# Sheet1.net
KiCad netlist of a schematic drawn in Altium Designer
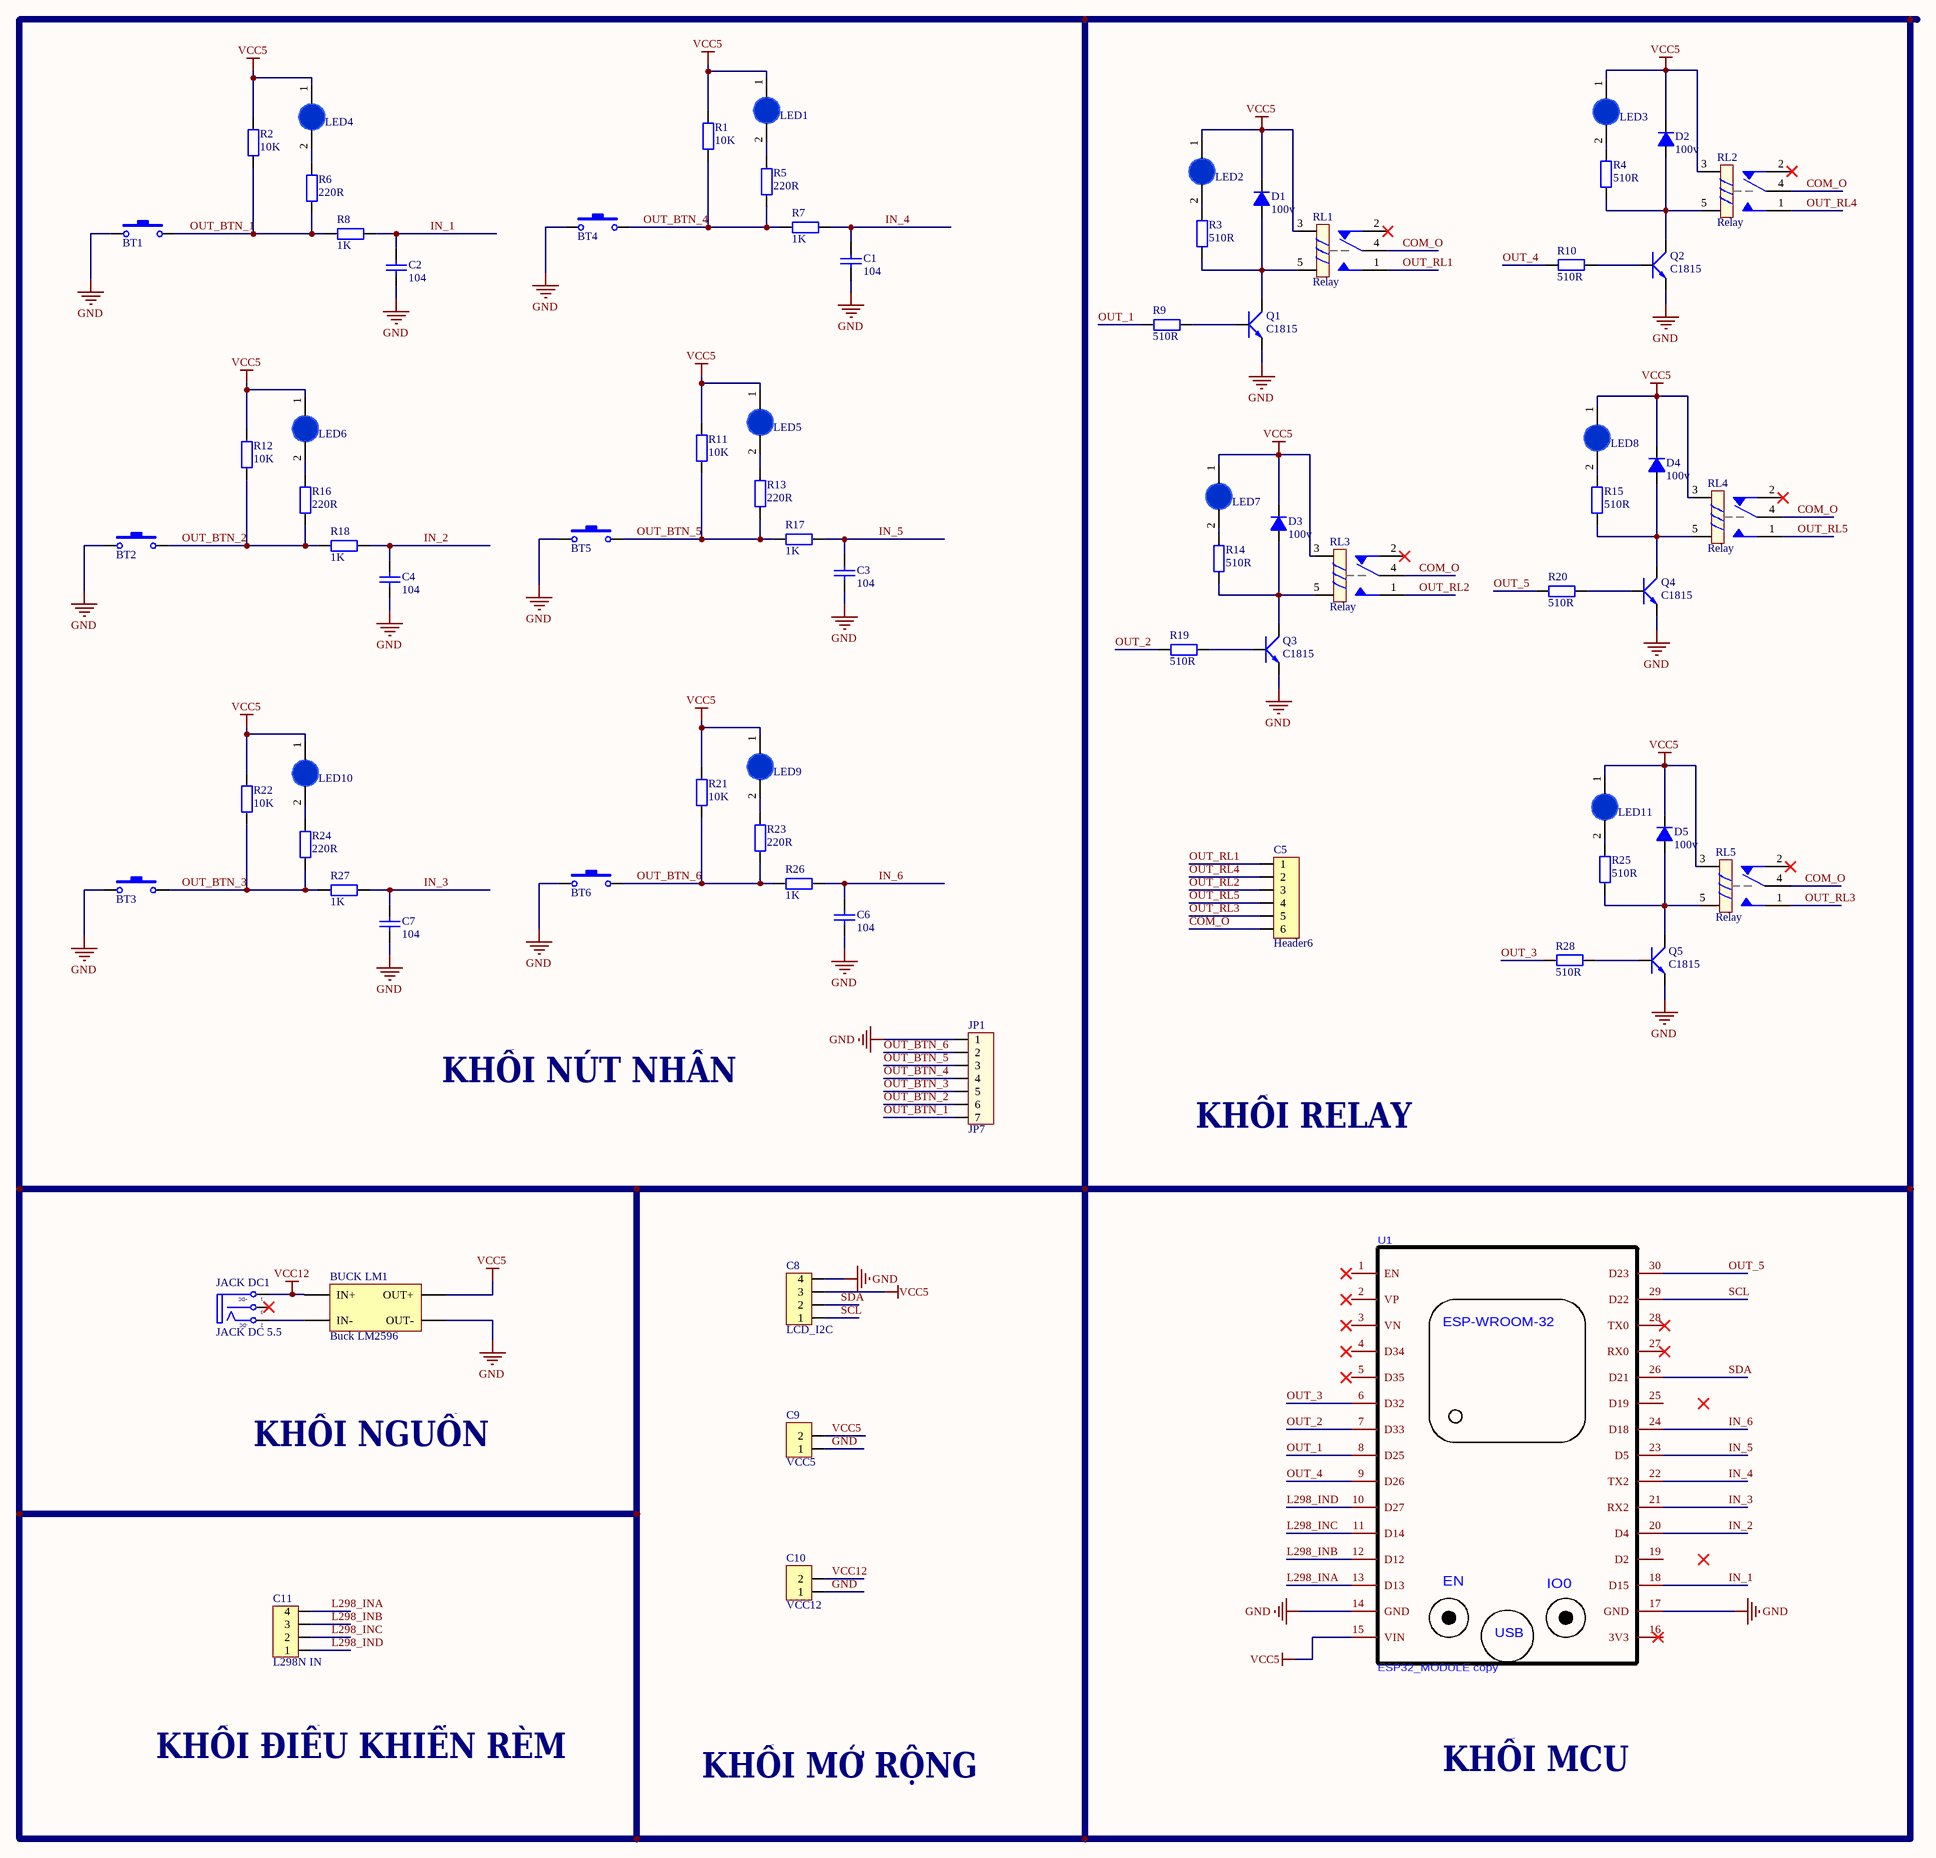
[diagram p0: Sheet1.SchDoc]

(export (version "E")
  (design (tool "Eeschema 10.0.6"))
  (components
    (comp (ref "BT1")
      (value "Nut Nhan 2 Chan SMD 3x6x2.5")
      (footprint "Nut Nhan 2 Chan SMD 3x6x2.5")
      (libsource (lib "Altium_Lib_by_KhueNguyenCreator") (part "Nut Nhan 2 Chan SMD 3x6x2.5"))
    )
    (comp (ref "BT2")
      (value "Nut Nhan 2 Chan SMD 3x6x2.5")
      (footprint "Nut Nhan 2 Chan SMD 3x6x2.5")
      (libsource (lib "Altium_Lib_by_KhueNguyenCreator") (part "Nut Nhan 2 Chan SMD 3x6x2.5"))
    )
    (comp (ref "BT3")
      (value "Nut Nhan 2 Chan SMD 3x6x2.5")
      (footprint "Nut Nhan 2 Chan SMD 3x6x2.5")
      (libsource (lib "Altium_Lib_by_KhueNguyenCreator") (part "Nut Nhan 2 Chan SMD 3x6x2.5"))
    )
    (comp (ref "BT4")
      (value "Nut Nhan 2 Chan SMD 3x6x2.5")
      (footprint "Nut Nhan 2 Chan SMD 3x6x2.5")
      (libsource (lib "Altium_Lib_by_KhueNguyenCreator") (part "Nut Nhan 2 Chan SMD 3x6x2.5"))
    )
    (comp (ref "BT5")
      (value "Nut Nhan 2 Chan SMD 3x6x2.5")
      (footprint "Nut Nhan 2 Chan SMD 3x6x2.5")
      (libsource (lib "Altium_Lib_by_KhueNguyenCreator") (part "Nut Nhan 2 Chan SMD 3x6x2.5"))
    )
    (comp (ref "BT6")
      (value "Nut Nhan 2 Chan SMD 3x6x2.5")
      (footprint "Nut Nhan 2 Chan SMD 3x6x2.5")
      (libsource (lib "Altium_Lib_by_KhueNguyenCreator") (part "Nut Nhan 2 Chan SMD 3x6x2.5"))
    )
    (comp (ref "BUCK LM1")
      (value "Buck LM2596")
      (footprint "BUCK LM2596")
      (libsource (lib "myLib_v1") (part "Buck LM2596"))
    )
    (comp (ref "C1")
      (value "104")
      (footprint "tu gom")
      (description "Cắm")
      (libsource (lib "Altium_Lib_by_KhueNguyenCreator") (part "Tu gom 104 50V"))
    )
    (comp (ref "C2")
      (value "104")
      (footprint "tu gom")
      (description "Cắm")
      (libsource (lib "Altium_Lib_by_KhueNguyenCreator") (part "Tu gom 104 50V"))
    )
    (comp (ref "C3")
      (value "104")
      (footprint "tu gom")
      (description "Cắm")
      (libsource (lib "Altium_Lib_by_KhueNguyenCreator") (part "Tu gom 104 50V"))
    )
    (comp (ref "C4")
      (value "104")
      (footprint "tu gom")
      (description "Cắm")
      (libsource (lib "Altium_Lib_by_KhueNguyenCreator") (part "Tu gom 104 50V"))
    )
    (comp (ref "C5")
      (value "Header6")
      (footprint "Header6")
      (description "Header IDC, 6 x 1 Pin Vertical 2.54mm Pitch (Non-Boxed, Male)")
      (fields
        (field (name "MANUFACTURER") "Würth Elektronik eiSos GmbH")
        (field (name "PARTNO") "613002143121")
        (field (name "CREATED BY") "Karrer Zheng")
      )
      (libsource (lib "myLib_v1") (part "Header6"))
    )
    (comp (ref "C6")
      (value "104")
      (footprint "tu gom")
      (description "Cắm")
      (libsource (lib "Altium_Lib_by_KhueNguyenCreator") (part "Tu gom 104 50V"))
    )
    (comp (ref "C7")
      (value "104")
      (footprint "tu gom")
      (description "Cắm")
      (libsource (lib "Altium_Lib_by_KhueNguyenCreator") (part "Tu gom 104 50V"))
    )
    (comp (ref "C8")
      (value "LCD_I2C")
      (footprint "Header4")
      (description "Header IDC, 4 x 1 Pin Vertical 2.54mm Pitch (Non-Boxed, Male)")
      (fields
        (field (name "MANUFACTURER") "Würth Elektronik eiSos GmbH")
        (field (name "PARTNO") "613002143121")
        (field (name "CREATED BY") "Karrer Zheng")
      )
      (libsource (lib "myLib_v1") (part "Header4"))
    )
    (comp (ref "C9")
      (value "VCC5")
      (footprint "Header2")
      (description "Header IDC, 2 x 1 Pin Vertical 2.54mm Pitch (Non-Boxed, Male)")
      (fields
        (field (name "MANUFACTURER") "Würth Elektronik eiSos GmbH")
        (field (name "PARTNO") "613002143121")
        (field (name "CREATED BY") "Karrer Zheng")
      )
      (libsource (lib "myLib_v1") (part "Header2"))
    )
    (comp (ref "C10")
      (value "VCC12")
      (footprint "Header2")
      (description "Header IDC, 2 x 1 Pin Vertical 2.54mm Pitch (Non-Boxed, Male)")
      (fields
        (field (name "MANUFACTURER") "Würth Elektronik eiSos GmbH")
        (field (name "PARTNO") "613002143121")
        (field (name "CREATED BY") "Karrer Zheng")
      )
      (libsource (lib "myLib_v1") (part "Header2"))
    )
    (comp (ref "C11")
      (value "L298N IN")
      (footprint "Header4")
      (description "Header IDC, 4 x 1 Pin Vertical 2.54mm Pitch (Non-Boxed, Male)")
      (fields
        (field (name "MANUFACTURER") "Würth Elektronik eiSos GmbH")
        (field (name "PARTNO") "613002143121")
        (field (name "CREATED BY") "Karrer Zheng")
      )
      (libsource (lib "myLib_v1") (part "Header4"))
    )
    (comp (ref "D1")
      (value "100v")
      (footprint "DIODE 0.5A")
      (description "Cắm")
      (libsource (lib "Altium_Lib_by_KhueNguyenCreator") (part "Diode 1N4148"))
    )
    (comp (ref "D2")
      (value "100v")
      (footprint "DIODE 0.5A")
      (description "Cắm")
      (libsource (lib "Altium_Lib_by_KhueNguyenCreator") (part "Diode 1N4148"))
    )
    (comp (ref "D3")
      (value "100v")
      (footprint "DIODE 0.5A")
      (description "Cắm")
      (libsource (lib "Altium_Lib_by_KhueNguyenCreator") (part "Diode 1N4148"))
    )
    (comp (ref "D4")
      (value "100v")
      (footprint "DIODE 0.5A")
      (description "Cắm")
      (libsource (lib "Altium_Lib_by_KhueNguyenCreator") (part "Diode 1N4148"))
    )
    (comp (ref "D5")
      (value "100v")
      (footprint "DIODE 0.5A")
      (description "Cắm")
      (libsource (lib "Altium_Lib_by_KhueNguyenCreator") (part "Diode 1N4148"))
    )
    (comp (ref "JACK DC1")
      (value "JACK DC 5.5")
      (footprint "JACK DC 5.5")
      (libsource (lib "Altium_Lib_by_KhueNguyenCreator") (part "JACK DC 5.5"))
    )
    (comp (ref "JP1")
      (value "JP7")
      (footprint "Header7")
      (description "Connector 7")
      (libsource (lib "myLib_v1") (part "Header7"))
    )
    (comp (ref "LED1")
      (value "LED 3mm")
      (footprint "LED-3MM-BLUE")
      (description "Cắm")
      (libsource (lib "myLib_v1") (part "LED 3mm Xanh Duong"))
    )
    (comp (ref "LED2")
      (value "LED 3mm")
      (footprint "LED-3MM-BLUE")
      (description "Cắm")
      (libsource (lib "myLib_v1") (part "LED 3mm Xanh Duong"))
    )
    (comp (ref "LED3")
      (value "LED 3mm")
      (footprint "LED-3MM-BLUE")
      (description "Cắm")
      (libsource (lib "myLib_v1") (part "LED 3mm Xanh Duong"))
    )
    (comp (ref "LED4")
      (value "LED 3mm")
      (footprint "LED-3MM-BLUE")
      (description "Cắm")
      (libsource (lib "myLib_v1") (part "LED 3mm Xanh Duong"))
    )
    (comp (ref "LED5")
      (value "LED 3mm")
      (footprint "LED-3MM-BLUE")
      (description "Cắm")
      (libsource (lib "myLib_v1") (part "LED 3mm Xanh Duong"))
    )
    (comp (ref "LED6")
      (value "LED 3mm")
      (footprint "LED-3MM-BLUE")
      (description "Cắm")
      (libsource (lib "myLib_v1") (part "LED 3mm Xanh Duong"))
    )
    (comp (ref "LED7")
      (value "LED 3mm")
      (footprint "LED-3MM-BLUE")
      (description "Cắm")
      (libsource (lib "myLib_v1") (part "LED 3mm Xanh Duong"))
    )
    (comp (ref "LED8")
      (value "LED 3mm")
      (footprint "LED-3MM-BLUE")
      (description "Cắm")
      (libsource (lib "myLib_v1") (part "LED 3mm Xanh Duong"))
    )
    (comp (ref "LED9")
      (value "LED 3mm")
      (footprint "LED-3MM-BLUE")
      (description "Cắm")
      (libsource (lib "myLib_v1") (part "LED 3mm Xanh Duong"))
    )
    (comp (ref "LED10")
      (value "LED 3mm")
      (footprint "LED-3MM-BLUE")
      (description "Cắm")
      (libsource (lib "myLib_v1") (part "LED 3mm Xanh Duong"))
    )
    (comp (ref "LED11")
      (value "LED 3mm")
      (footprint "LED-3MM-BLUE")
      (description "Cắm")
      (libsource (lib "myLib_v1") (part "LED 3mm Xanh Duong"))
    )
    (comp (ref "Q1")
      (value "C1815")
      (footprint "C1815_cam")
      (description "NPN 600mW, ECB")
      (libsource (lib "myLib_v1") (part "C1815"))
    )
    (comp (ref "Q2")
      (value "C1815")
      (footprint "C1815_cam")
      (description "NPN 600mW, ECB")
      (libsource (lib "myLib_v1") (part "C1815"))
    )
    (comp (ref "Q3")
      (value "C1815")
      (footprint "C1815_cam")
      (description "NPN 600mW, ECB")
      (libsource (lib "myLib_v1") (part "C1815"))
    )
    (comp (ref "Q4")
      (value "C1815")
      (footprint "C1815_cam")
      (description "NPN 600mW, ECB")
      (libsource (lib "myLib_v1") (part "C1815"))
    )
    (comp (ref "Q5")
      (value "C1815")
      (footprint "C1815_cam")
      (description "NPN 600mW, ECB")
      (libsource (lib "myLib_v1") (part "C1815"))
    )
    (comp (ref "R1")
      (value "10K")
      (footprint "R1/4W")
      (description "Resistor 1/4W")
      (libsource (lib "myLib_v1") (part "R1/4W"))
    )
    (comp (ref "R2")
      (value "10K")
      (footprint "R1/4W")
      (description "Resistor 1/4W")
      (libsource (lib "myLib_v1") (part "R1/4W"))
    )
    (comp (ref "R3")
      (value "510R")
      (footprint "R1/4W")
      (description "Resistor 1/4W")
      (libsource (lib "myLib_v1") (part "R1/4W"))
    )
    (comp (ref "R4")
      (value "510R")
      (footprint "R1/4W")
      (description "Resistor 1/4W")
      (libsource (lib "myLib_v1") (part "R1/4W"))
    )
    (comp (ref "R5")
      (value "220R")
      (footprint "R1/4W")
      (description "Resistor 1/4W")
      (libsource (lib "myLib_v1") (part "R1/4W"))
    )
    (comp (ref "R6")
      (value "220R")
      (footprint "R1/4W")
      (description "Resistor 1/4W")
      (libsource (lib "myLib_v1") (part "R1/4W"))
    )
    (comp (ref "R7")
      (value "1K")
      (footprint "R1/4W")
      (description "Resistor 1/4W")
      (libsource (lib "myLib_v1") (part "R1/4W"))
    )
    (comp (ref "R8")
      (value "1K")
      (footprint "R1/4W")
      (description "Resistor 1/4W")
      (libsource (lib "myLib_v1") (part "R1/4W"))
    )
    (comp (ref "R9")
      (value "510R")
      (footprint "R1/4W")
      (description "Resistor 1/4W")
      (libsource (lib "myLib_v1") (part "R1/4W"))
    )
    (comp (ref "R10")
      (value "510R")
      (footprint "R1/4W")
      (description "Resistor 1/4W")
      (libsource (lib "myLib_v1") (part "R1/4W"))
    )
    (comp (ref "R11")
      (value "10K")
      (footprint "R1/4W")
      (description "Resistor 1/4W")
      (libsource (lib "myLib_v1") (part "R1/4W"))
    )
    (comp (ref "R12")
      (value "10K")
      (footprint "R1/4W")
      (description "Resistor 1/4W")
      (libsource (lib "myLib_v1") (part "R1/4W"))
    )
    (comp (ref "R13")
      (value "220R")
      (footprint "R1/4W")
      (description "Resistor 1/4W")
      (libsource (lib "myLib_v1") (part "R1/4W"))
    )
    (comp (ref "R14")
      (value "510R")
      (footprint "R1/4W")
      (description "Resistor 1/4W")
      (libsource (lib "myLib_v1") (part "R1/4W"))
    )
    (comp (ref "R15")
      (value "510R")
      (footprint "R1/4W")
      (description "Resistor 1/4W")
      (libsource (lib "myLib_v1") (part "R1/4W"))
    )
    (comp (ref "R16")
      (value "220R")
      (footprint "R1/4W")
      (description "Resistor 1/4W")
      (libsource (lib "myLib_v1") (part "R1/4W"))
    )
    (comp (ref "R17")
      (value "1K")
      (footprint "R1/4W")
      (description "Resistor 1/4W")
      (libsource (lib "myLib_v1") (part "R1/4W"))
    )
    (comp (ref "R18")
      (value "1K")
      (footprint "R1/4W")
      (description "Resistor 1/4W")
      (libsource (lib "myLib_v1") (part "R1/4W"))
    )
    (comp (ref "R19")
      (value "510R")
      (footprint "R1/4W")
      (description "Resistor 1/4W")
      (libsource (lib "myLib_v1") (part "R1/4W"))
    )
    (comp (ref "R20")
      (value "510R")
      (footprint "R1/4W")
      (description "Resistor 1/4W")
      (libsource (lib "myLib_v1") (part "R1/4W"))
    )
    (comp (ref "R21")
      (value "10K")
      (footprint "R1/4W")
      (description "Resistor 1/4W")
      (libsource (lib "myLib_v1") (part "R1/4W"))
    )
    (comp (ref "R22")
      (value "10K")
      (footprint "R1/4W")
      (description "Resistor 1/4W")
      (libsource (lib "myLib_v1") (part "R1/4W"))
    )
    (comp (ref "R23")
      (value "220R")
      (footprint "R1/4W")
      (description "Resistor 1/4W")
      (libsource (lib "myLib_v1") (part "R1/4W"))
    )
    (comp (ref "R24")
      (value "220R")
      (footprint "R1/4W")
      (description "Resistor 1/4W")
      (libsource (lib "myLib_v1") (part "R1/4W"))
    )
    (comp (ref "R25")
      (value "510R")
      (footprint "R1/4W")
      (description "Resistor 1/4W")
      (libsource (lib "myLib_v1") (part "R1/4W"))
    )
    (comp (ref "R26")
      (value "1K")
      (footprint "R1/4W")
      (description "Resistor 1/4W")
      (libsource (lib "myLib_v1") (part "R1/4W"))
    )
    (comp (ref "R27")
      (value "1K")
      (footprint "R1/4W")
      (description "Resistor 1/4W")
      (libsource (lib "myLib_v1") (part "R1/4W"))
    )
    (comp (ref "R28")
      (value "510R")
      (footprint "R1/4W")
      (description "Resistor 1/4W")
      (libsource (lib "myLib_v1") (part "R1/4W"))
    )
    (comp (ref "RL1")
      (value "Relay")
      (footprint "RELAY_SRA_05VDC_SL_C")
      (description "Relay 5 Chan")
      (libsource (lib "myLib_v1") (part "RL_SRA-05VDC-SL-C"))
    )
    (comp (ref "RL2")
      (value "Relay")
      (footprint "RELAY_SRA_05VDC_SL_C")
      (description "Relay 5 Chan")
      (libsource (lib "myLib_v1") (part "RL_SRA-05VDC-SL-C"))
    )
    (comp (ref "RL3")
      (value "Relay")
      (footprint "RELAY_SRA_05VDC_SL_C")
      (description "Relay 5 Chan")
      (libsource (lib "myLib_v1") (part "RL_SRA-05VDC-SL-C"))
    )
    (comp (ref "RL4")
      (value "Relay")
      (footprint "RELAY_SRA_05VDC_SL_C")
      (description "Relay 5 Chan")
      (libsource (lib "myLib_v1") (part "RL_SRA-05VDC-SL-C"))
    )
    (comp (ref "RL5")
      (value "Relay")
      (footprint "RELAY_SRA_05VDC_SL_C")
      (description "Relay 5 Chan")
      (libsource (lib "myLib_v1") (part "RL_SRA-05VDC-SL-C"))
    )
    (comp (ref "U1")
      (value "ESP32_MODULE copy")
      (footprint "ESP32-WIFIMODULE-FOOTPRINT")
      (libsource (lib "myLib_v1") (part "ESP32_MODULE copy"))
    )
  )
  (nets
    (net (code "1") (name "/COM_O") (class "Default")
      (node (ref "C5") (pin "6") (pinfunction "6_6") (pintype "passive"))
      (node (ref "RL1") (pin "4") (pinfunction "4_4") (pintype "passive"))
      (node (ref "RL2") (pin "4") (pinfunction "4_4") (pintype "passive"))
      (node (ref "RL3") (pin "4") (pinfunction "4_4") (pintype "passive"))
      (node (ref "RL4") (pin "4") (pinfunction "4_4") (pintype "passive"))
      (node (ref "RL5") (pin "4") (pinfunction "4_4") (pintype "passive"))
    )
    (net (code "2") (name "/IN_1") (class "Default")
      (node (ref "C2") (pin "1") (pinfunction "1_1") (pintype "passive"))
      (node (ref "R8") (pin "1") (pinfunction "1_1") (pintype "passive"))
      (node (ref "U1") (pin "18") (pinfunction "D15_18") (pintype "passive"))
    )
    (net (code "3") (name "/IN_2") (class "Default")
      (node (ref "C4") (pin "1") (pinfunction "1_1") (pintype "passive"))
      (node (ref "R18") (pin "1") (pinfunction "1_1") (pintype "passive"))
      (node (ref "U1") (pin "20") (pinfunction "D4_20") (pintype "passive"))
    )
    (net (code "4") (name "/IN_3") (class "Default")
      (node (ref "C7") (pin "1") (pinfunction "1_1") (pintype "passive"))
      (node (ref "R27") (pin "1") (pinfunction "1_1") (pintype "passive"))
      (node (ref "U1") (pin "21") (pinfunction "RX2_21") (pintype "passive"))
    )
    (net (code "5") (name "/IN_4") (class "Default")
      (node (ref "C1") (pin "1") (pinfunction "1_1") (pintype "passive"))
      (node (ref "R7") (pin "1") (pinfunction "1_1") (pintype "passive"))
      (node (ref "U1") (pin "22") (pinfunction "TX2_22") (pintype "passive"))
    )
    (net (code "6") (name "/IN_5") (class "Default")
      (node (ref "C3") (pin "1") (pinfunction "1_1") (pintype "passive"))
      (node (ref "R17") (pin "1") (pinfunction "1_1") (pintype "passive"))
      (node (ref "U1") (pin "23") (pinfunction "D5_23") (pintype "passive"))
    )
    (net (code "7") (name "/IN_6") (class "Default")
      (node (ref "C6") (pin "1") (pinfunction "1_1") (pintype "passive"))
      (node (ref "R26") (pin "1") (pinfunction "1_1") (pintype "passive"))
      (node (ref "U1") (pin "24") (pinfunction "D18_24") (pintype "passive"))
    )
    (net (code "8") (name "/L298_INA") (class "Default")
      (node (ref "C11") (pin "4") (pinfunction "4_4") (pintype "passive"))
      (node (ref "U1") (pin "13") (pinfunction "D13_13") (pintype "passive"))
    )
    (net (code "9") (name "/L298_INB") (class "Default")
      (node (ref "C11") (pin "3") (pinfunction "3_3") (pintype "passive"))
      (node (ref "U1") (pin "12") (pinfunction "D12_12") (pintype "passive"))
    )
    (net (code "10") (name "/L298_INC") (class "Default")
      (node (ref "C11") (pin "2") (pinfunction "2_2") (pintype "passive"))
      (node (ref "U1") (pin "11") (pinfunction "D14_11") (pintype "passive"))
    )
    (net (code "11") (name "/L298_IND") (class "Default")
      (node (ref "C11") (pin "1") (pinfunction "1_1") (pintype "passive"))
      (node (ref "U1") (pin "10") (pinfunction "D27_10") (pintype "passive"))
    )
    (net (code "12") (name "/OUT_1") (class "Default")
      (node (ref "R9") (pin "1") (pinfunction "1_1") (pintype "passive"))
      (node (ref "U1") (pin "8") (pinfunction "D25_8") (pintype "passive"))
    )
    (net (code "13") (name "/OUT_2") (class "Default")
      (node (ref "R19") (pin "1") (pinfunction "1_1") (pintype "passive"))
      (node (ref "U1") (pin "7") (pinfunction "D33_7") (pintype "passive"))
    )
    (net (code "14") (name "/OUT_3") (class "Default")
      (node (ref "R28") (pin "1") (pinfunction "1_1") (pintype "passive"))
      (node (ref "U1") (pin "6") (pinfunction "D32_6") (pintype "passive"))
    )
    (net (code "15") (name "/OUT_4") (class "Default")
      (node (ref "R10") (pin "1") (pinfunction "1_1") (pintype "passive"))
      (node (ref "U1") (pin "9") (pinfunction "D26_9") (pintype "passive"))
    )
    (net (code "16") (name "/OUT_5") (class "Default")
      (node (ref "R20") (pin "1") (pinfunction "1_1") (pintype "passive"))
      (node (ref "U1") (pin "30") (pinfunction "D23_30") (pintype "passive"))
    )
    (net (code "17") (name "/OUT_BTN_1") (class "Default")
      (node (ref "BT1") (pin "2") (pinfunction "2_2") (pintype "passive"))
      (node (ref "JP1") (pin "7") (pinfunction "7_7") (pintype "passive"))
      (node (ref "R2") (pin "1") (pinfunction "1_1") (pintype "passive"))
      (node (ref "R6") (pin "1") (pinfunction "1_1") (pintype "passive"))
      (node (ref "R8") (pin "2") (pinfunction "2_2") (pintype "passive"))
    )
    (net (code "18") (name "/OUT_BTN_2") (class "Default")
      (node (ref "BT2") (pin "2") (pinfunction "2_2") (pintype "passive"))
      (node (ref "JP1") (pin "6") (pinfunction "6_6") (pintype "passive"))
      (node (ref "R12") (pin "1") (pinfunction "1_1") (pintype "passive"))
      (node (ref "R16") (pin "1") (pinfunction "1_1") (pintype "passive"))
      (node (ref "R18") (pin "2") (pinfunction "2_2") (pintype "passive"))
    )
    (net (code "19") (name "/OUT_BTN_3") (class "Default")
      (node (ref "BT3") (pin "2") (pinfunction "2_2") (pintype "passive"))
      (node (ref "JP1") (pin "5") (pinfunction "5_5") (pintype "passive"))
      (node (ref "R22") (pin "1") (pinfunction "1_1") (pintype "passive"))
      (node (ref "R24") (pin "1") (pinfunction "1_1") (pintype "passive"))
      (node (ref "R27") (pin "2") (pinfunction "2_2") (pintype "passive"))
    )
    (net (code "20") (name "/OUT_BTN_4") (class "Default")
      (node (ref "BT4") (pin "2") (pinfunction "2_2") (pintype "passive"))
      (node (ref "JP1") (pin "4") (pinfunction "4_4") (pintype "passive"))
      (node (ref "R1") (pin "1") (pinfunction "1_1") (pintype "passive"))
      (node (ref "R5") (pin "1") (pinfunction "1_1") (pintype "passive"))
      (node (ref "R7") (pin "2") (pinfunction "2_2") (pintype "passive"))
    )
    (net (code "21") (name "/OUT_BTN_5") (class "Default")
      (node (ref "BT5") (pin "2") (pinfunction "2_2") (pintype "passive"))
      (node (ref "JP1") (pin "3") (pinfunction "3_3") (pintype "passive"))
      (node (ref "R11") (pin "1") (pinfunction "1_1") (pintype "passive"))
      (node (ref "R13") (pin "1") (pinfunction "1_1") (pintype "passive"))
      (node (ref "R17") (pin "2") (pinfunction "2_2") (pintype "passive"))
    )
    (net (code "22") (name "/OUT_BTN_6") (class "Default")
      (node (ref "BT6") (pin "2") (pinfunction "2_2") (pintype "passive"))
      (node (ref "JP1") (pin "2") (pinfunction "2_2") (pintype "passive"))
      (node (ref "R21") (pin "1") (pinfunction "1_1") (pintype "passive"))
      (node (ref "R23") (pin "1") (pinfunction "1_1") (pintype "passive"))
      (node (ref "R26") (pin "2") (pinfunction "2_2") (pintype "passive"))
    )
    (net (code "23") (name "/OUT_RL1") (class "Default")
      (node (ref "C5") (pin "1") (pinfunction "1_1") (pintype "passive"))
      (node (ref "RL1") (pin "1") (pinfunction "1_1") (pintype "passive"))
    )
    (net (code "24") (name "/OUT_RL2") (class "Default")
      (node (ref "C5") (pin "3") (pinfunction "3_3") (pintype "passive"))
      (node (ref "RL3") (pin "1") (pinfunction "1_1") (pintype "passive"))
    )
    (net (code "25") (name "/OUT_RL3") (class "Default")
      (node (ref "C5") (pin "5") (pinfunction "5_5") (pintype "passive"))
      (node (ref "RL5") (pin "1") (pinfunction "1_1") (pintype "passive"))
    )
    (net (code "26") (name "/OUT_RL4") (class "Default")
      (node (ref "C5") (pin "2") (pinfunction "2_2") (pintype "passive"))
      (node (ref "RL2") (pin "1") (pinfunction "1_1") (pintype "passive"))
    )
    (net (code "27") (name "/OUT_RL5") (class "Default")
      (node (ref "C5") (pin "4") (pinfunction "4_4") (pintype "passive"))
      (node (ref "RL4") (pin "1") (pinfunction "1_1") (pintype "passive"))
    )
    (net (code "28") (name "/SCL") (class "Default")
      (node (ref "C8") (pin "1") (pinfunction "1_1") (pintype "passive"))
      (node (ref "U1") (pin "29") (pinfunction "D22_29") (pintype "passive"))
    )
    (net (code "29") (name "/SDA") (class "Default")
      (node (ref "C8") (pin "2") (pinfunction "2_2") (pintype "passive"))
      (node (ref "U1") (pin "26") (pinfunction "D21_26") (pintype "passive"))
    )
    (net (code "30") (name "GND") (class "Default")
      (node (ref "BT1") (pin "1") (pinfunction "1_1") (pintype "passive"))
      (node (ref "BT2") (pin "1") (pinfunction "1_1") (pintype "passive"))
      (node (ref "BT3") (pin "1") (pinfunction "1_1") (pintype "passive"))
      (node (ref "BT4") (pin "1") (pinfunction "1_1") (pintype "passive"))
      (node (ref "BT5") (pin "1") (pinfunction "1_1") (pintype "passive"))
      (node (ref "BT6") (pin "1") (pinfunction "1_1") (pintype "passive"))
      (node (ref "BUCK LM1") (pin "3") (pinfunction "OUT-_3") (pintype "passive"))
      (node (ref "C1") (pin "2") (pinfunction "2_2") (pintype "passive"))
      (node (ref "C10") (pin "1") (pinfunction "1_1") (pintype "passive"))
      (node (ref "C2") (pin "2") (pinfunction "2_2") (pintype "passive"))
      (node (ref "C3") (pin "2") (pinfunction "2_2") (pintype "passive"))
      (node (ref "C4") (pin "2") (pinfunction "2_2") (pintype "passive"))
      (node (ref "C6") (pin "2") (pinfunction "2_2") (pintype "passive"))
      (node (ref "C7") (pin "2") (pinfunction "2_2") (pintype "passive"))
      (node (ref "C8") (pin "4") (pinfunction "4_4") (pintype "passive"))
      (node (ref "C9") (pin "1") (pinfunction "1_1") (pintype "passive"))
      (node (ref "JP1") (pin "1") (pinfunction "1_1") (pintype "passive"))
      (node (ref "Q1") (pin "1") (pinfunction "E_1") (pintype "passive"))
      (node (ref "Q2") (pin "1") (pinfunction "E_1") (pintype "passive"))
      (node (ref "Q3") (pin "1") (pinfunction "E_1") (pintype "passive"))
      (node (ref "Q4") (pin "1") (pinfunction "E_1") (pintype "passive"))
      (node (ref "Q5") (pin "1") (pinfunction "E_1") (pintype "passive"))
      (node (ref "U1") (pin "14") (pinfunction "GND_14") (pintype "passive"))
      (node (ref "U1") (pin "17") (pinfunction "GND_17") (pintype "passive"))
    )
    (net (code "31") (name "Net-(BUCK LM1-IN-)") (class "Default")
      (node (ref "BUCK LM1") (pin "2") (pinfunction "IN-_2") (pintype "passive"))
      (node (ref "JACK DC1") (pin "2") (pinfunction "TN_2") (pintype "passive"))
    )
    (net (code "32") (name "Net-(D1-A)") (class "Default")
      (node (ref "D1") (pin "1") (pinfunction "A_1") (pintype "passive"))
      (node (ref "Q1") (pin "2") (pinfunction "C_2") (pintype "passive"))
      (node (ref "R3") (pin "2") (pinfunction "2_2") (pintype "passive"))
      (node (ref "RL1") (pin "5") (pinfunction "5_5") (pintype "passive"))
    )
    (net (code "33") (name "Net-(D2-A)") (class "Default")
      (node (ref "D2") (pin "1") (pinfunction "A_1") (pintype "passive"))
      (node (ref "Q2") (pin "2") (pinfunction "C_2") (pintype "passive"))
      (node (ref "R4") (pin "2") (pinfunction "2_2") (pintype "passive"))
      (node (ref "RL2") (pin "5") (pinfunction "5_5") (pintype "passive"))
    )
    (net (code "34") (name "Net-(D3-A)") (class "Default")
      (node (ref "D3") (pin "1") (pinfunction "A_1") (pintype "passive"))
      (node (ref "Q3") (pin "2") (pinfunction "C_2") (pintype "passive"))
      (node (ref "R14") (pin "2") (pinfunction "2_2") (pintype "passive"))
      (node (ref "RL3") (pin "5") (pinfunction "5_5") (pintype "passive"))
    )
    (net (code "35") (name "Net-(D4-A)") (class "Default")
      (node (ref "D4") (pin "1") (pinfunction "A_1") (pintype "passive"))
      (node (ref "Q4") (pin "2") (pinfunction "C_2") (pintype "passive"))
      (node (ref "R15") (pin "2") (pinfunction "2_2") (pintype "passive"))
      (node (ref "RL4") (pin "5") (pinfunction "5_5") (pintype "passive"))
    )
    (net (code "36") (name "Net-(D5-A)") (class "Default")
      (node (ref "D5") (pin "1") (pinfunction "A_1") (pintype "passive"))
      (node (ref "Q5") (pin "2") (pinfunction "C_2") (pintype "passive"))
      (node (ref "R25") (pin "2") (pinfunction "2_2") (pintype "passive"))
      (node (ref "RL5") (pin "5") (pinfunction "5_5") (pintype "passive"))
    )
    (net (code "37") (name "Net-(LED1-K)") (class "Default")
      (node (ref "LED1") (pin "2") (pinfunction "K_2") (pintype "passive"))
      (node (ref "R5") (pin "2") (pinfunction "2_2") (pintype "passive"))
    )
    (net (code "38") (name "Net-(LED2-K)") (class "Default")
      (node (ref "LED2") (pin "2") (pinfunction "K_2") (pintype "passive"))
      (node (ref "R3") (pin "1") (pinfunction "1_1") (pintype "passive"))
    )
    (net (code "39") (name "Net-(LED3-K)") (class "Default")
      (node (ref "LED3") (pin "2") (pinfunction "K_2") (pintype "passive"))
      (node (ref "R4") (pin "1") (pinfunction "1_1") (pintype "passive"))
    )
    (net (code "40") (name "Net-(LED4-K)") (class "Default")
      (node (ref "LED4") (pin "2") (pinfunction "K_2") (pintype "passive"))
      (node (ref "R6") (pin "2") (pinfunction "2_2") (pintype "passive"))
    )
    (net (code "41") (name "Net-(LED5-K)") (class "Default")
      (node (ref "LED5") (pin "2") (pinfunction "K_2") (pintype "passive"))
      (node (ref "R13") (pin "2") (pinfunction "2_2") (pintype "passive"))
    )
    (net (code "42") (name "Net-(LED6-K)") (class "Default")
      (node (ref "LED6") (pin "2") (pinfunction "K_2") (pintype "passive"))
      (node (ref "R16") (pin "2") (pinfunction "2_2") (pintype "passive"))
    )
    (net (code "43") (name "Net-(LED7-K)") (class "Default")
      (node (ref "LED7") (pin "2") (pinfunction "K_2") (pintype "passive"))
      (node (ref "R14") (pin "1") (pinfunction "1_1") (pintype "passive"))
    )
    (net (code "44") (name "Net-(LED8-K)") (class "Default")
      (node (ref "LED8") (pin "2") (pinfunction "K_2") (pintype "passive"))
      (node (ref "R15") (pin "1") (pinfunction "1_1") (pintype "passive"))
    )
    (net (code "45") (name "Net-(LED9-K)") (class "Default")
      (node (ref "LED9") (pin "2") (pinfunction "K_2") (pintype "passive"))
      (node (ref "R23") (pin "2") (pinfunction "2_2") (pintype "passive"))
    )
    (net (code "46") (name "Net-(LED10-K)") (class "Default")
      (node (ref "LED10") (pin "2") (pinfunction "K_2") (pintype "passive"))
      (node (ref "R24") (pin "2") (pinfunction "2_2") (pintype "passive"))
    )
    (net (code "47") (name "Net-(LED11-K)") (class "Default")
      (node (ref "LED11") (pin "2") (pinfunction "K_2") (pintype "passive"))
      (node (ref "R25") (pin "1") (pinfunction "1_1") (pintype "passive"))
    )
    (net (code "48") (name "Net-(Q1-B)") (class "Default")
      (node (ref "Q1") (pin "3") (pinfunction "B_3") (pintype "passive"))
      (node (ref "R9") (pin "2") (pinfunction "2_2") (pintype "passive"))
    )
    (net (code "49") (name "Net-(Q2-B)") (class "Default")
      (node (ref "Q2") (pin "3") (pinfunction "B_3") (pintype "passive"))
      (node (ref "R10") (pin "2") (pinfunction "2_2") (pintype "passive"))
    )
    (net (code "50") (name "Net-(Q3-B)") (class "Default")
      (node (ref "Q3") (pin "3") (pinfunction "B_3") (pintype "passive"))
      (node (ref "R19") (pin "2") (pinfunction "2_2") (pintype "passive"))
    )
    (net (code "51") (name "Net-(Q4-B)") (class "Default")
      (node (ref "Q4") (pin "3") (pinfunction "B_3") (pintype "passive"))
      (node (ref "R20") (pin "2") (pinfunction "2_2") (pintype "passive"))
    )
    (net (code "52") (name "Net-(Q5-B)") (class "Default")
      (node (ref "Q5") (pin "3") (pinfunction "B_3") (pintype "passive"))
      (node (ref "R28") (pin "2") (pinfunction "2_2") (pintype "passive"))
    )
    (net (code "53") (name "VCC5") (class "Default")
      (node (ref "BUCK LM1") (pin "4") (pinfunction "OUT+_4") (pintype "passive"))
      (node (ref "C8") (pin "3") (pinfunction "3_3") (pintype "passive"))
      (node (ref "C9") (pin "2") (pinfunction "2_2") (pintype "passive"))
      (node (ref "D1") (pin "2") (pinfunction "K_2") (pintype "passive"))
      (node (ref "D2") (pin "2") (pinfunction "K_2") (pintype "passive"))
      (node (ref "D3") (pin "2") (pinfunction "K_2") (pintype "passive"))
      (node (ref "D4") (pin "2") (pinfunction "K_2") (pintype "passive"))
      (node (ref "D5") (pin "2") (pinfunction "K_2") (pintype "passive"))
      (node (ref "LED1") (pin "1") (pinfunction "A_1") (pintype "passive"))
      (node (ref "LED10") (pin "1") (pinfunction "A_1") (pintype "passive"))
      (node (ref "LED11") (pin "1") (pinfunction "A_1") (pintype "passive"))
      (node (ref "LED2") (pin "1") (pinfunction "A_1") (pintype "passive"))
      (node (ref "LED3") (pin "1") (pinfunction "A_1") (pintype "passive"))
      (node (ref "LED4") (pin "1") (pinfunction "A_1") (pintype "passive"))
      (node (ref "LED5") (pin "1") (pinfunction "A_1") (pintype "passive"))
      (node (ref "LED6") (pin "1") (pinfunction "A_1") (pintype "passive"))
      (node (ref "LED7") (pin "1") (pinfunction "A_1") (pintype "passive"))
      (node (ref "LED8") (pin "1") (pinfunction "A_1") (pintype "passive"))
      (node (ref "LED9") (pin "1") (pinfunction "A_1") (pintype "passive"))
      (node (ref "R1") (pin "2") (pinfunction "2_2") (pintype "passive"))
      (node (ref "R11") (pin "2") (pinfunction "2_2") (pintype "passive"))
      (node (ref "R12") (pin "2") (pinfunction "2_2") (pintype "passive"))
      (node (ref "R2") (pin "2") (pinfunction "2_2") (pintype "passive"))
      (node (ref "R21") (pin "2") (pinfunction "2_2") (pintype "passive"))
      (node (ref "R22") (pin "2") (pinfunction "2_2") (pintype "passive"))
      (node (ref "RL1") (pin "3") (pinfunction "3_3") (pintype "passive"))
      (node (ref "RL2") (pin "3") (pinfunction "3_3") (pintype "passive"))
      (node (ref "RL3") (pin "3") (pinfunction "3_3") (pintype "passive"))
      (node (ref "RL4") (pin "3") (pinfunction "3_3") (pintype "passive"))
      (node (ref "RL5") (pin "3") (pinfunction "3_3") (pintype "passive"))
      (node (ref "U1") (pin "15") (pinfunction "VIN_15") (pintype "passive"))
    )
    (net (code "54") (name "VCC12") (class "Default")
      (node (ref "BUCK LM1") (pin "1") (pinfunction "IN+_1") (pintype "passive"))
      (node (ref "C10") (pin "2") (pinfunction "2_2") (pintype "passive"))
      (node (ref "JACK DC1") (pin "1") (pinfunction "T_1") (pintype "passive"))
    )
    (net (code "55") (name "unconnected-(JACK DC1-S-Pad3)") (class "Default")
      (node (ref "JACK DC1") (pin "3") (pinfunction "S_3") (pintype "power_in+no_connect"))
    )
    (net (code "56") (name "unconnected-(RL1-Pad2)") (class "Default")
      (node (ref "RL1") (pin "2") (pinfunction "2_2") (pintype "passive+no_connect"))
    )
    (net (code "57") (name "unconnected-(RL2-Pad2)") (class "Default")
      (node (ref "RL2") (pin "2") (pinfunction "2_2") (pintype "passive+no_connect"))
    )
    (net (code "58") (name "unconnected-(RL3-Pad2)") (class "Default")
      (node (ref "RL3") (pin "2") (pinfunction "2_2") (pintype "passive+no_connect"))
    )
    (net (code "59") (name "unconnected-(RL4-Pad2)") (class "Default")
      (node (ref "RL4") (pin "2") (pinfunction "2_2") (pintype "passive+no_connect"))
    )
    (net (code "60") (name "unconnected-(RL5-Pad2)") (class "Default")
      (node (ref "RL5") (pin "2") (pinfunction "2_2") (pintype "passive+no_connect"))
    )
    (net (code "61") (name "unconnected-(U1-3V3-Pad16)") (class "Default")
      (node (ref "U1") (pin "16") (pinfunction "3V3_16") (pintype "passive"))
    )
    (net (code "62") (name "unconnected-(U1-D2-Pad19)") (class "Default")
      (node (ref "U1") (pin "19") (pinfunction "D2_19") (pintype "passive"))
    )
    (net (code "63") (name "unconnected-(U1-D19-Pad25)") (class "Default")
      (node (ref "U1") (pin "25") (pinfunction "D19_25") (pintype "passive"))
    )
    (net (code "64") (name "unconnected-(U1-D34-Pad4)") (class "Default")
      (node (ref "U1") (pin "4") (pinfunction "D34_4") (pintype "passive"))
    )
    (net (code "65") (name "unconnected-(U1-D35-Pad5)") (class "Default")
      (node (ref "U1") (pin "5") (pinfunction "D35_5") (pintype "passive"))
    )
    (net (code "66") (name "unconnected-(U1-EN-Pad1)") (class "Default")
      (node (ref "U1") (pin "1") (pinfunction "EN_1") (pintype "passive"))
    )
    (net (code "67") (name "unconnected-(U1-RX0-Pad27)") (class "Default")
      (node (ref "U1") (pin "27") (pinfunction "RX0_27") (pintype "passive"))
    )
    (net (code "68") (name "unconnected-(U1-TX0-Pad28)") (class "Default")
      (node (ref "U1") (pin "28") (pinfunction "TX0_28") (pintype "passive"))
    )
    (net (code "69") (name "unconnected-(U1-VN-Pad3)") (class "Default")
      (node (ref "U1") (pin "3") (pinfunction "VN_3") (pintype "passive"))
    )
    (net (code "70") (name "unconnected-(U1-VP-Pad2)") (class "Default")
      (node (ref "U1") (pin "2") (pinfunction "VP_2") (pintype "passive"))
    )
  )
)
